# USB.net
KiCad netlist of a schematic drawn in EasyEDA Pro
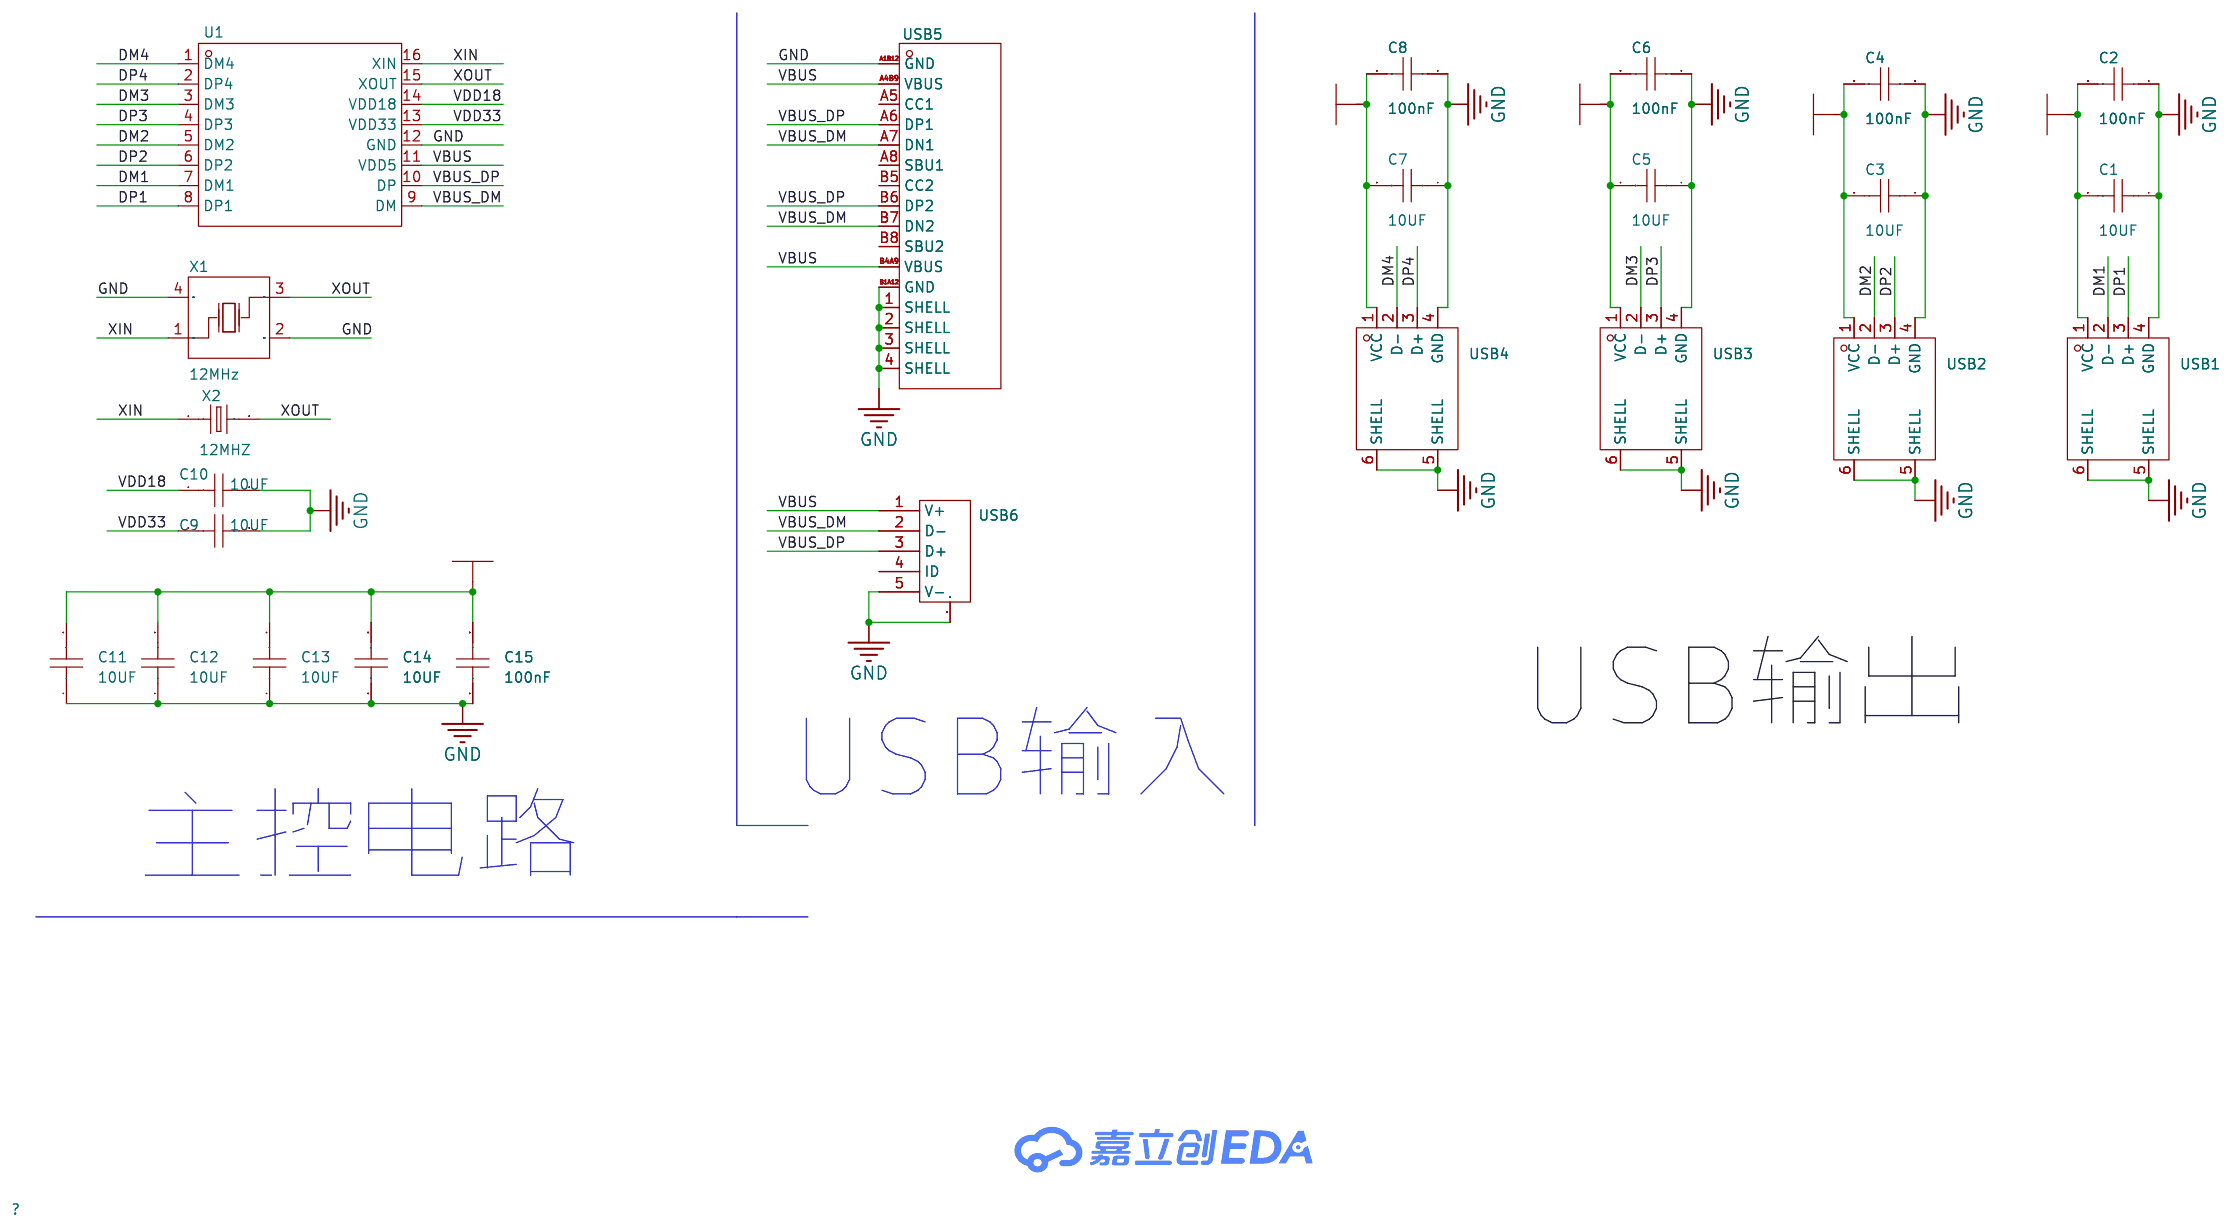
[diagram p0: schematic sheet]

(export (version "E")
  (design (tool "Eeschema 10.0.6"))
  (components
    (comp (ref "C1")
      (value "10UF")
      (footprint "easyedapro:C0805")
      (description "容值:100nF;精度:±10%;额定电压:50V;温度系数:X7R;")
      (libsource (lib "easyedapro") (part "C1210X7R475K630NT"))
    )
    (comp (ref "C2")
      (value "100nF")
      (footprint "easyedapro:C0805")
      (description "容值:100nF;精度:±10%;额定电压:50V;温度系数:X7R;")
      (libsource (lib "easyedapro") (part "C1210X7R475K630NT"))
    )
    (comp (ref "C3")
      (value "10UF")
      (footprint "easyedapro:C0805")
      (description "容值:100nF;精度:±10%;额定电压:50V;温度系数:X7R;")
      (libsource (lib "easyedapro") (part "C1210X7R475K630NT"))
    )
    (comp (ref "C4")
      (value "100nF")
      (footprint "easyedapro:C0805")
      (description "容值:100nF;精度:±10%;额定电压:50V;温度系数:X7R;")
      (libsource (lib "easyedapro") (part "C1210X7R475K630NT"))
    )
    (comp (ref "C5")
      (value "10UF")
      (footprint "easyedapro:C0805")
      (description "容值:100nF;精度:±10%;额定电压:50V;温度系数:X7R;")
      (libsource (lib "easyedapro") (part "C1210X7R475K630NT"))
    )
    (comp (ref "C6")
      (value "100nF")
      (footprint "easyedapro:C0805")
      (description "容值:100nF;精度:±10%;额定电压:50V;温度系数:X7R;")
      (libsource (lib "easyedapro") (part "C1210X7R475K630NT"))
    )
    (comp (ref "C7")
      (value "10UF")
      (footprint "easyedapro:C0805")
      (description "容值:100nF;精度:±10%;额定电压:50V;温度系数:X7R;")
      (libsource (lib "easyedapro") (part "C1210X7R475K630NT"))
    )
    (comp (ref "C8")
      (value "100nF")
      (footprint "easyedapro:C0805")
      (description "容值:100nF;精度:±10%;额定电压:50V;温度系数:X7R;")
      (libsource (lib "easyedapro") (part "C1210X7R475K630NT"))
    )
    (comp (ref "C9")
      (value "10UF")
      (footprint "easyedapro:C0805")
      (description "容值:100nF;精度:±10%;额定电压:50V;温度系数:X7R;")
      (libsource (lib "easyedapro") (part "C1210X7R475K630NT"))
    )
    (comp (ref "C10")
      (value "10UF")
      (footprint "easyedapro:C0805")
      (description "容值:100nF;精度:±10%;额定电压:50V;温度系数:X7R;")
      (libsource (lib "easyedapro") (part "C1210X7R475K630NT"))
    )
    (comp (ref "C11")
      (value "10UF")
      (footprint "easyedapro:C0805")
      (description "容值:100nF;精度:±10%;额定电压:50V;温度系数:X7R;")
      (libsource (lib "easyedapro") (part "C1210X7R475K630NT"))
    )
    (comp (ref "C12")
      (value "10UF")
      (footprint "easyedapro:C0805")
      (description "容值:100nF;精度:±10%;额定电压:50V;温度系数:X7R;")
      (libsource (lib "easyedapro") (part "C1210X7R475K630NT"))
    )
    (comp (ref "C13")
      (value "10UF")
      (footprint "easyedapro:C0805")
      (description "容值:100nF;精度:±10%;额定电压:50V;温度系数:X7R;")
      (libsource (lib "easyedapro") (part "C1210X7R475K630NT"))
    )
    (comp (ref "C14")
      (value "10UF")
      (footprint "easyedapro:C0805")
      (description "容值:100nF;精度:±10%;额定电压:50V;温度系数:X7R;")
      (libsource (lib "easyedapro") (part "C1210X7R475K630NT"))
    )
    (comp (ref "C15")
      (value "100nF")
      (footprint "easyedapro:C0805")
      (description "容值:100nF;精度:±10%;额定电压:50V;温度系数:X7R;")
      (libsource (lib "easyedapro") (part "C1210X7R475K630NT"))
    )
    (comp (ref "U1")
      (value "~")
      (footprint "easyedapro:SOP-16_L10.0-W3.9-P1.27-LS6.0-BL")
      (description "类型:-;协议类别:-;驱动器/接收器数:-;数据速率:-;")
      (fields (field (name "Manufacturer Part") "SL2.1A") (field (name "Manufacturer") "CoreChips(和芯润德)"))
      (libsource (lib "easyedapro") (part "SL2.1A"))
    )
    (comp (ref "USB1")
      (value "~")
      (footprint "easyedapro:USB-A-TH_916-362A1114Y10210")
      (description "连接器类型:Type-A;标准:USB 2.0;公母:母座;触点数量:4;端口数量:1;安装方式:直插;额定电流 - 电源:5A;工作温度范围:-55~+85;")
      (fields (field (name "Manufacturer Part") "916-362A1094Y10210") (field (name "Manufacturer") "精拓金"))
      (libsource (lib "easyedapro") (part "916-362A1094Y10210"))
    )
    (comp (ref "USB2")
      (value "~")
      (footprint "easyedapro:USB-A-TH_916-362A1114Y10210")
      (description "连接器类型:Type-A;标准:USB 2.0;公母:母座;触点数量:4;端口数量:1;安装方式:直插;额定电流 - 电源:5A;工作温度范围:-55~+85;")
      (fields (field (name "Manufacturer Part") "916-362A1094Y10210") (field (name "Manufacturer") "精拓金"))
      (libsource (lib "easyedapro") (part "916-362A1094Y10210"))
    )
    (comp (ref "USB3")
      (value "~")
      (footprint "easyedapro:USB-A-TH_916-362A1114Y10210")
      (description "连接器类型:Type-A;标准:USB 2.0;公母:母座;触点数量:4;端口数量:1;安装方式:直插;额定电流 - 电源:5A;工作温度范围:-55~+85;")
      (fields (field (name "Manufacturer Part") "916-362A1094Y10210") (field (name "Manufacturer") "精拓金"))
      (libsource (lib "easyedapro") (part "916-362A1094Y10210"))
    )
    (comp (ref "USB4")
      (value "~")
      (footprint "easyedapro:USB-A-TH_916-362A1114Y10210")
      (description "连接器类型:Type-A;标准:USB 2.0;公母:母座;触点数量:4;端口数量:1;安装方式:直插;额定电流 - 电源:5A;工作温度范围:-55~+85;")
      (fields (field (name "Manufacturer Part") "916-362A1094Y10210") (field (name "Manufacturer") "精拓金"))
      (libsource (lib "easyedapro") (part "916-362A1094Y10210"))
    )
    (comp (ref "USB5")
      (value "~")
      (footprint "easyedapro:USB-C-SMD_TYPE-C16PIN")
      (description "连接器类型:Type-C;标准:-;公母:母座;触点数量:16;端口数量:1;安装方式:卧贴;额定电流 - 电源:3A;工作温度范围:-40~+85;")
      (fields (field (name "Manufacturer Part") "TYPE-C16PIN") (field (name "Manufacturer") "SHOU HAN(首韩)"))
      (libsource (lib "easyedapro") (part "TYPE-C16PIN"))
    )
    (comp (ref "USB6")
      (value "~")
      (footprint "easyedapro:MICRO-USB-SMD_5P-P0.65-H-F_C10418")
      (description "连接器类型:Micro-B;标准:USB 2.0;公母:母座;触点数量:5;端口数量:1;额定电流 - 电源:1A;")
      (fields (field (name "Manufacturer Part") "920-E52A2021S10100") (field (name "Manufacturer") "精拓金"))
      (libsource (lib "easyedapro") (part "micro USBFemale"))
    )
    (comp (ref "X1")
      (value "12MHz")
      (footprint "easyedapro:OSC-SMD_4P-L3.2-W2.5-BL")
      (description "晶振类型:贴片无源晶振;频率:16MHz;频率公差:±10ppm;频率稳定度:±30ppm;负载电容:9pF;工作温度:-40~+85;")
      (fields (field (name "Manufacturer Part") "X322516MLB4SI") (field (name "Manufacturer") "YXC扬兴科技"))
      (libsource (lib "easyedapro") (part "X322516MLB4SI"))
    )
    (comp (ref "X2")
      (value "12MHZ")
      (footprint "easyedapro:HC-49US_L11.5-W4.5-P4.88")
      (description "晶振类型:-;频率:-;频率公差:-;频率稳定度:-;负载电容:-;工作温度:-;")
      (fields
        (field (name "Manufacturer Part") "XIHCELNANF-12MHZ")
        (field (name "Manufacturer") "TAITIEN(泰艺电子)")
      )
      (libsource (lib "easyedapro") (part "XIHCELNANF-12MHZ"))
    )
  )
  (nets
    (net (code "1") (name "/DM1") (class "Default")
      (node (ref "U1") (pin "7") (pinfunction "DM1_7") (pintype "input"))
      (node (ref "USB1") (pin "2") (pinfunction "D-_2") (pintype "input"))
    )
    (net (code "2") (name "/DM2") (class "Default")
      (node (ref "U1") (pin "5") (pinfunction "DM2_5") (pintype "input"))
      (node (ref "USB2") (pin "2") (pinfunction "D-_2") (pintype "input"))
    )
    (net (code "3") (name "/DM3") (class "Default")
      (node (ref "U1") (pin "3") (pinfunction "DM3_3") (pintype "input"))
      (node (ref "USB3") (pin "2") (pinfunction "D-_2") (pintype "input"))
    )
    (net (code "4") (name "/DM4") (class "Default")
      (node (ref "U1") (pin "1") (pinfunction "DM4_1") (pintype "input"))
      (node (ref "USB4") (pin "2") (pinfunction "D-_2") (pintype "input"))
    )
    (net (code "5") (name "/DP1") (class "Default")
      (node (ref "U1") (pin "8") (pinfunction "DP1_8") (pintype "input"))
      (node (ref "USB1") (pin "3") (pinfunction "D+_3") (pintype "input"))
    )
    (net (code "6") (name "/DP2") (class "Default")
      (node (ref "U1") (pin "6") (pinfunction "DP2_6") (pintype "input"))
      (node (ref "USB2") (pin "3") (pinfunction "D+_3") (pintype "input"))
    )
    (net (code "7") (name "/DP3") (class "Default")
      (node (ref "U1") (pin "4") (pinfunction "DP3_4") (pintype "input"))
      (node (ref "USB3") (pin "3") (pinfunction "D+_3") (pintype "input"))
    )
    (net (code "8") (name "/DP4") (class "Default")
      (node (ref "U1") (pin "2") (pinfunction "DP4_2") (pintype "input"))
      (node (ref "USB4") (pin "3") (pinfunction "D+_3") (pintype "input"))
    )
    (net (code "9") (name "/VBUS_DM") (class "Default")
      (node (ref "U1") (pin "9") (pinfunction "DM_9") (pintype "input"))
      (node (ref "USB5") (pin "A7") (pinfunction "DN1_A7") (pintype "input"))
      (node (ref "USB5") (pin "B7") (pinfunction "DN2_B7") (pintype "input"))
      (node (ref "USB6") (pin "2") (pinfunction "D-_2") (pintype "input"))
    )
    (net (code "10") (name "/VBUS_DP") (class "Default")
      (node (ref "U1") (pin "10") (pinfunction "DP_10") (pintype "input"))
      (node (ref "USB5") (pin "A6") (pinfunction "DP1_A6") (pintype "input"))
      (node (ref "USB5") (pin "B6") (pinfunction "DP2_B6") (pintype "input"))
      (node (ref "USB6") (pin "3") (pinfunction "D+_3") (pintype "input"))
    )
    (net (code "11") (name "/VDD18") (class "Default")
      (node (ref "C10") (pin "1") (pinfunction "1_1") (pintype "input"))
      (node (ref "U1") (pin "14") (pinfunction "VDD18_14") (pintype "input"))
    )
    (net (code "12") (name "/VDD33") (class "Default")
      (node (ref "C9") (pin "1") (pinfunction "1_1") (pintype "input"))
      (node (ref "U1") (pin "13") (pinfunction "VDD33_13") (pintype "input"))
    )
    (net (code "13") (name "/XIN") (class "Default")
      (node (ref "U1") (pin "16") (pinfunction "XIN_16") (pintype "input"))
      (node (ref "X1") (pin "1") (pinfunction "OSC1_1") (pintype "input"))
      (node (ref "X2") (pin "1") (pinfunction "1_1") (pintype "input"))
    )
    (net (code "14") (name "/XOUT") (class "Default")
      (node (ref "U1") (pin "15") (pinfunction "XOUT_15") (pintype "input"))
      (node (ref "X1") (pin "3") (pinfunction "OSC2_3") (pintype "input"))
      (node (ref "X2") (pin "2") (pinfunction "2_2") (pintype "input"))
    )
    (net (code "15") (name "GND") (class "Default")
      (node (ref "C1") (pin "1") (pinfunction "1_1") (pintype "input"))
      (node (ref "C10") (pin "2") (pinfunction "2_2") (pintype "input"))
      (node (ref "C11") (pin "1") (pinfunction "1_1") (pintype "input"))
      (node (ref "C12") (pin "1") (pinfunction "1_1") (pintype "input"))
      (node (ref "C13") (pin "1") (pinfunction "1_1") (pintype "input"))
      (node (ref "C14") (pin "1") (pinfunction "1_1") (pintype "input"))
      (node (ref "C15") (pin "1") (pinfunction "1_1") (pintype "input"))
      (node (ref "C2") (pin "1") (pinfunction "1_1") (pintype "input"))
      (node (ref "C3") (pin "1") (pinfunction "1_1") (pintype "input"))
      (node (ref "C4") (pin "1") (pinfunction "1_1") (pintype "input"))
      (node (ref "C5") (pin "1") (pinfunction "1_1") (pintype "input"))
      (node (ref "C6") (pin "1") (pinfunction "1_1") (pintype "input"))
      (node (ref "C7") (pin "1") (pinfunction "1_1") (pintype "input"))
      (node (ref "C8") (pin "1") (pinfunction "1_1") (pintype "input"))
      (node (ref "C9") (pin "2") (pinfunction "2_2") (pintype "input"))
      (node (ref "U1") (pin "12") (pinfunction "GND_12") (pintype "input"))
      (node (ref "USB1") (pin "4") (pinfunction "GND_4") (pintype "input"))
      (node (ref "USB1") (pin "5") (pinfunction "SHELL_5") (pintype "input"))
      (node (ref "USB1") (pin "6") (pinfunction "SHELL_6") (pintype "input"))
      (node (ref "USB2") (pin "4") (pinfunction "GND_4") (pintype "input"))
      (node (ref "USB2") (pin "5") (pinfunction "SHELL_5") (pintype "input"))
      (node (ref "USB2") (pin "6") (pinfunction "SHELL_6") (pintype "input"))
      (node (ref "USB3") (pin "4") (pinfunction "GND_4") (pintype "input"))
      (node (ref "USB3") (pin "5") (pinfunction "SHELL_5") (pintype "input"))
      (node (ref "USB3") (pin "6") (pinfunction "SHELL_6") (pintype "input"))
      (node (ref "USB4") (pin "4") (pinfunction "GND_4") (pintype "input"))
      (node (ref "USB4") (pin "5") (pinfunction "SHELL_5") (pintype "input"))
      (node (ref "USB4") (pin "6") (pinfunction "SHELL_6") (pintype "input"))
      (node (ref "USB5") (pin "1") (pinfunction "SHELL_1") (pintype "input"))
      (node (ref "USB5") (pin "2") (pinfunction "SHELL_2") (pintype "input"))
      (node (ref "USB5") (pin "3") (pinfunction "SHELL_3") (pintype "input"))
      (node (ref "USB5") (pin "4") (pinfunction "SHELL_4") (pintype "input"))
      (node (ref "USB5") (pin "A1B12") (pinfunction "GND_A1B12") (pintype "input"))
      (node (ref "USB5") (pin "B1A12") (pinfunction "GND_B1A12") (pintype "input"))
      (node (ref "USB6") (pin "0") (pinfunction "MTN_0") (pintype "input"))
      (node (ref "USB6") (pin "5") (pinfunction "V-_5") (pintype "input"))
      (node (ref "X1") (pin "2") (pinfunction "GND_2") (pintype "input"))
      (node (ref "X1") (pin "4") (pinfunction "GND_4") (pintype "input"))
    )
    (net (code "16") (name "VBUS") (class "Default")
      (node (ref "C1") (pin "2") (pinfunction "2_2") (pintype "input"))
      (node (ref "C11") (pin "2") (pinfunction "2_2") (pintype "input"))
      (node (ref "C12") (pin "2") (pinfunction "2_2") (pintype "input"))
      (node (ref "C13") (pin "2") (pinfunction "2_2") (pintype "input"))
      (node (ref "C14") (pin "2") (pinfunction "2_2") (pintype "input"))
      (node (ref "C15") (pin "2") (pinfunction "2_2") (pintype "input"))
      (node (ref "C2") (pin "2") (pinfunction "2_2") (pintype "input"))
      (node (ref "C3") (pin "2") (pinfunction "2_2") (pintype "input"))
      (node (ref "C4") (pin "2") (pinfunction "2_2") (pintype "input"))
      (node (ref "C5") (pin "2") (pinfunction "2_2") (pintype "input"))
      (node (ref "C6") (pin "2") (pinfunction "2_2") (pintype "input"))
      (node (ref "C7") (pin "2") (pinfunction "2_2") (pintype "input"))
      (node (ref "C8") (pin "2") (pinfunction "2_2") (pintype "input"))
      (node (ref "U1") (pin "11") (pinfunction "VDD5_11") (pintype "input"))
      (node (ref "USB1") (pin "1") (pinfunction "VCC_1") (pintype "input"))
      (node (ref "USB2") (pin "1") (pinfunction "VCC_1") (pintype "input"))
      (node (ref "USB3") (pin "1") (pinfunction "VCC_1") (pintype "input"))
      (node (ref "USB4") (pin "1") (pinfunction "VCC_1") (pintype "input"))
      (node (ref "USB5") (pin "A4B9") (pinfunction "VBUS_A4B9") (pintype "input"))
      (node (ref "USB5") (pin "B4A9") (pinfunction "VBUS_B4A9") (pintype "input"))
      (node (ref "USB6") (pin "1") (pinfunction "V+_1") (pintype "input"))
    )
    (net (code "17") (name "unconnected-(USB5-CC1-PadA5)") (class "Default")
      (node (ref "USB5") (pin "A5") (pinfunction "CC1_A5") (pintype "input"))
    )
    (net (code "18") (name "unconnected-(USB5-CC2-PadB5)") (class "Default")
      (node (ref "USB5") (pin "B5") (pinfunction "CC2_B5") (pintype "input"))
    )
    (net (code "19") (name "unconnected-(USB5-SBU1-PadA8)") (class "Default")
      (node (ref "USB5") (pin "A8") (pinfunction "SBU1_A8") (pintype "input"))
    )
    (net (code "20") (name "unconnected-(USB5-SBU2-PadB8)") (class "Default")
      (node (ref "USB5") (pin "B8") (pinfunction "SBU2_B8") (pintype "input"))
    )
    (net (code "21") (name "unconnected-(USB6-ID-Pad4)") (class "Default")
      (node (ref "USB6") (pin "4") (pinfunction "ID_4") (pintype "input"))
    )
  )
)
